# version1b.net
KiCad netlist of a schematic drawn in EAGLE
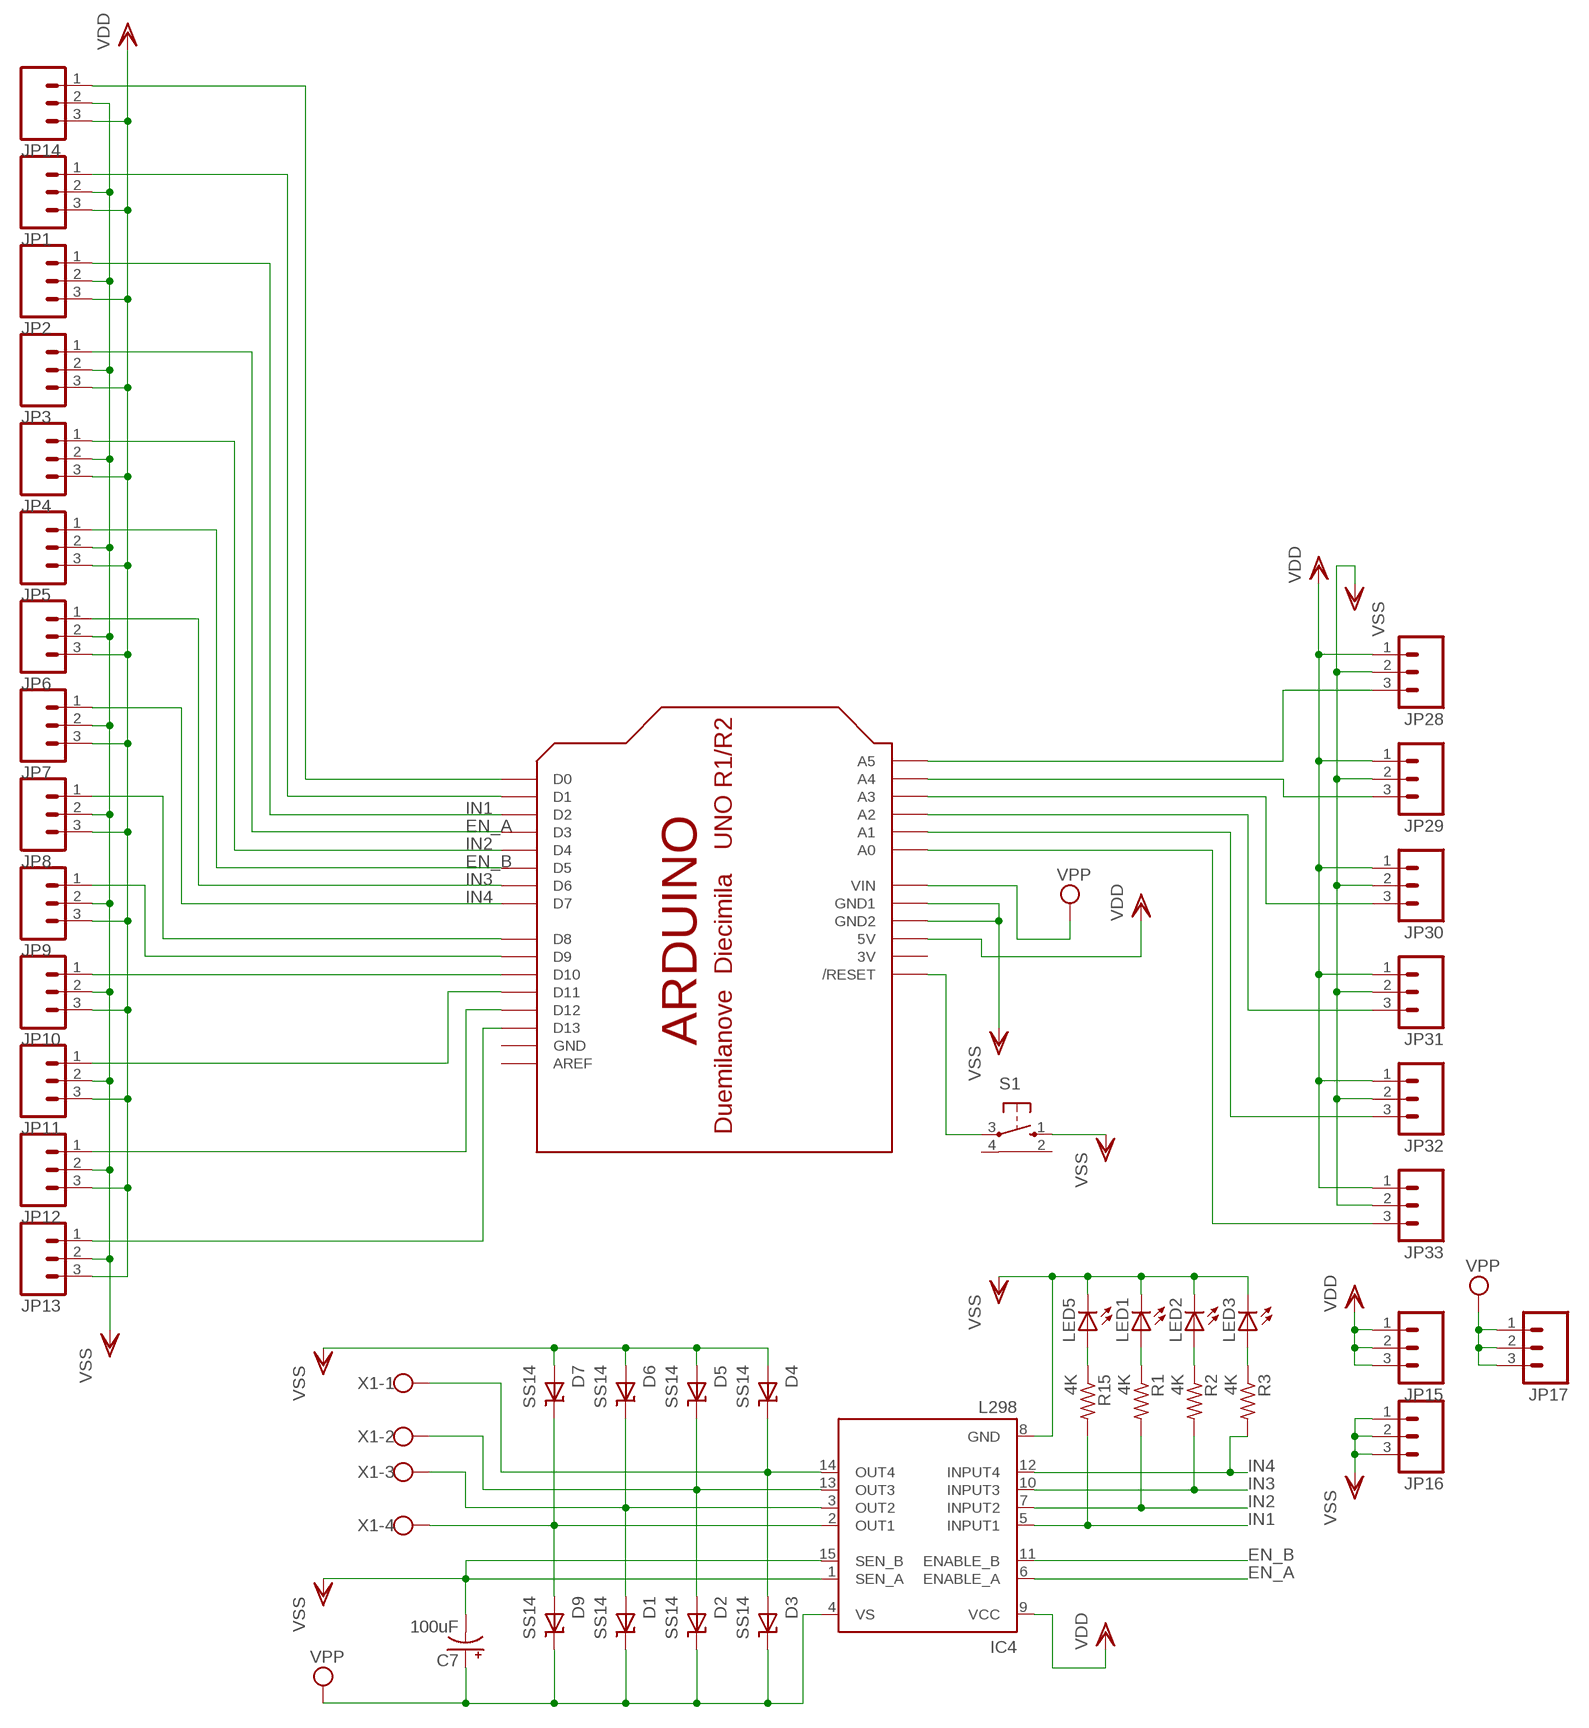
[diagram p0: schematic, sheet 1]

(export (version "E")
  (design (tool "Eeschema 10.0.6"))
  (components
    (comp (ref "C7")
      (value "100uF")
      (footprint "eagle-import:153CLV-0605")
      (libsource (lib "eagle-import") (part "CPOL-US153CLV-0605"))
    )
    (comp (ref "D1")
      (value "SS14")
      (footprint "eagle-import:SMA")
      (libsource (lib "eagle-import") (part "SS14"))
    )
    (comp (ref "D2")
      (value "SS14")
      (footprint "eagle-import:SMA")
      (libsource (lib "eagle-import") (part "SS14"))
    )
    (comp (ref "D3")
      (value "SS14")
      (footprint "eagle-import:SMA")
      (libsource (lib "eagle-import") (part "SS14"))
    )
    (comp (ref "D4")
      (value "SS14")
      (footprint "eagle-import:SMA")
      (libsource (lib "eagle-import") (part "SS14"))
    )
    (comp (ref "D5")
      (value "SS14")
      (footprint "eagle-import:SMA")
      (libsource (lib "eagle-import") (part "SS14"))
    )
    (comp (ref "D6")
      (value "SS14")
      (footprint "eagle-import:SMA")
      (libsource (lib "eagle-import") (part "SS14"))
    )
    (comp (ref "D7")
      (value "SS14")
      (footprint "eagle-import:SMA")
      (libsource (lib "eagle-import") (part "SS14"))
    )
    (comp (ref "D9")
      (value "SS14")
      (footprint "eagle-import:SMA")
      (libsource (lib "eagle-import") (part "SS14"))
    )
    (comp (ref "IC4")
      (value "L298")
      (footprint "eagle-import:MULTIWATT-15")
      (fields (field (name "MPN") "L298N"))
      (libsource (lib "eagle-import") (part "L298"))
    )
    (comp (ref "JP1")
      (value "M03PTH")
      (footprint "eagle-import:1X03")
      (libsource (lib "eagle-import") (part "M03PTH"))
    )
    (comp (ref "JP2")
      (value "M03PTH")
      (footprint "eagle-import:1X03")
      (libsource (lib "eagle-import") (part "M03PTH"))
    )
    (comp (ref "JP3")
      (value "M03PTH")
      (footprint "eagle-import:1X03")
      (libsource (lib "eagle-import") (part "M03PTH"))
    )
    (comp (ref "JP4")
      (value "M03PTH")
      (footprint "eagle-import:1X03")
      (libsource (lib "eagle-import") (part "M03PTH"))
    )
    (comp (ref "JP5")
      (value "M03PTH")
      (footprint "eagle-import:1X03")
      (libsource (lib "eagle-import") (part "M03PTH"))
    )
    (comp (ref "JP6")
      (value "M03PTH")
      (footprint "eagle-import:1X03")
      (libsource (lib "eagle-import") (part "M03PTH"))
    )
    (comp (ref "JP7")
      (value "M03PTH")
      (footprint "eagle-import:1X03")
      (libsource (lib "eagle-import") (part "M03PTH"))
    )
    (comp (ref "JP8")
      (value "M03PTH")
      (footprint "eagle-import:1X03")
      (libsource (lib "eagle-import") (part "M03PTH"))
    )
    (comp (ref "JP9")
      (value "M03PTH")
      (footprint "eagle-import:1X03")
      (libsource (lib "eagle-import") (part "M03PTH"))
    )
    (comp (ref "JP10")
      (value "M03PTH")
      (footprint "eagle-import:1X03")
      (libsource (lib "eagle-import") (part "M03PTH"))
    )
    (comp (ref "JP11")
      (value "M03PTH")
      (footprint "eagle-import:1X03")
      (libsource (lib "eagle-import") (part "M03PTH"))
    )
    (comp (ref "JP12")
      (value "M03PTH")
      (footprint "eagle-import:1X03")
      (libsource (lib "eagle-import") (part "M03PTH"))
    )
    (comp (ref "JP13")
      (value "M03PTH")
      (footprint "eagle-import:1X03")
      (libsource (lib "eagle-import") (part "M03PTH"))
    )
    (comp (ref "JP14")
      (value "M03PTH")
      (footprint "eagle-import:1X03")
      (libsource (lib "eagle-import") (part "M03PTH"))
    )
    (comp (ref "JP15")
      (value "M03PTH")
      (footprint "eagle-import:1X03")
      (libsource (lib "eagle-import") (part "M03PTH"))
    )
    (comp (ref "JP16")
      (value "M03PTH")
      (footprint "eagle-import:1X03")
      (libsource (lib "eagle-import") (part "M03PTH"))
    )
    (comp (ref "JP17")
      (value "M03PTH")
      (footprint "eagle-import:1X03")
      (libsource (lib "eagle-import") (part "M03PTH"))
    )
    (comp (ref "JP28")
      (value "M03PTH")
      (footprint "eagle-import:1X03")
      (libsource (lib "eagle-import") (part "M03PTH"))
    )
    (comp (ref "JP29")
      (value "M03PTH")
      (footprint "eagle-import:1X03")
      (libsource (lib "eagle-import") (part "M03PTH"))
    )
    (comp (ref "JP30")
      (value "M03PTH")
      (footprint "eagle-import:1X03")
      (libsource (lib "eagle-import") (part "M03PTH"))
    )
    (comp (ref "JP31")
      (value "M03PTH")
      (footprint "eagle-import:1X03")
      (libsource (lib "eagle-import") (part "M03PTH"))
    )
    (comp (ref "JP32")
      (value "M03PTH")
      (footprint "eagle-import:1X03")
      (libsource (lib "eagle-import") (part "M03PTH"))
    )
    (comp (ref "JP33")
      (value "M03PTH")
      (footprint "eagle-import:1X03")
      (libsource (lib "eagle-import") (part "M03PTH"))
    )
    (comp (ref "LED1")
      (value "LEDCHIP-LED0805")
      (footprint "eagle-import:CHIP-LED0805")
      (libsource (lib "eagle-import") (part "LEDCHIP-LED0805"))
    )
    (comp (ref "LED2")
      (value "LEDCHIP-LED0805")
      (footprint "eagle-import:CHIP-LED0805")
      (libsource (lib "eagle-import") (part "LEDCHIP-LED0805"))
    )
    (comp (ref "LED3")
      (value "LEDCHIP-LED0805")
      (footprint "eagle-import:CHIP-LED0805")
      (libsource (lib "eagle-import") (part "LEDCHIP-LED0805"))
    )
    (comp (ref "LED5")
      (value "LEDCHIP-LED0805")
      (footprint "eagle-import:CHIP-LED0805")
      (libsource (lib "eagle-import") (part "LEDCHIP-LED0805"))
    )
    (comp (ref "R1")
      (value "4K")
      (footprint "eagle-import:R0805")
      (libsource (lib "eagle-import") (part "R-US_R0805"))
    )
    (comp (ref "R2")
      (value "4K")
      (footprint "eagle-import:R0805")
      (libsource (lib "eagle-import") (part "R-US_R0805"))
    )
    (comp (ref "R3")
      (value "4K")
      (footprint "eagle-import:R0805")
      (libsource (lib "eagle-import") (part "R-US_R0805"))
    )
    (comp (ref "R15")
      (value "4K")
      (footprint "eagle-import:R0805")
      (libsource (lib "eagle-import") (part "R-US_R0805"))
    )
    (comp (ref "S1")
      (value "10-XX-RPAD")
      (footprint "eagle-import:B3F-10XX-RPAD")
      (libsource (lib "eagle-import") (part "10-XX-RPAD"))
    )
    (comp (ref "U$1")
      (value "ARDUINO-NOHOLE")
      (footprint "eagle-import:ARDUINO-NOHOLE")
      (libsource (lib "eagle-import") (part "ARDUINO-NOHOLE"))
    )
    (comp (ref "X1")
      (value "W237-4")
      (footprint "eagle-import:W237-4")
      (libsource (lib "eagle-import") (part "W237-4"))
    )
  )
  (nets
    (net (code "1") (name "/3V") (class "Default")
      (node (ref "U$1") (pin "3V") (pinfunction "3V_3V") (pintype "power_in"))
    )
    (net (code "2") (name "/EN_A") (class "Default")
      (node (ref "IC4") (pin "6") (pinfunction "ENABLE_A_6") (pintype "input"))
      (node (ref "JP3") (pin "1") (pinfunction "1_1") (pintype "passive"))
      (node (ref "U$1") (pin "D3") (pinfunction "D3_D3") (pintype "bidirectional"))
    )
    (net (code "3") (name "/EN_B") (class "Default")
      (node (ref "IC4") (pin "11") (pinfunction "ENABLE_B_11") (pintype "input"))
      (node (ref "JP5") (pin "1") (pinfunction "1_1") (pintype "passive"))
      (node (ref "U$1") (pin "D5") (pinfunction "D5_D5") (pintype "bidirectional"))
    )
    (net (code "4") (name "/GND") (class "Default")
      (node (ref "U$1") (pin "GND") (pinfunction "GND_GND") (pintype "power_in"))
    )
    (net (code "5") (name "/IN1") (class "Default")
      (node (ref "IC4") (pin "5") (pinfunction "INPUT1_5") (pintype "input"))
      (node (ref "JP2") (pin "1") (pinfunction "1_1") (pintype "passive"))
      (node (ref "R15") (pin "2") (pinfunction "2_2") (pintype "passive"))
      (node (ref "U$1") (pin "D2") (pinfunction "D2_D2") (pintype "bidirectional"))
    )
    (net (code "6") (name "/IN2") (class "Default")
      (node (ref "IC4") (pin "7") (pinfunction "INPUT2_7") (pintype "input"))
      (node (ref "JP4") (pin "1") (pinfunction "1_1") (pintype "passive"))
      (node (ref "R1") (pin "2") (pinfunction "2_2") (pintype "passive"))
      (node (ref "U$1") (pin "D4") (pinfunction "D4_D4") (pintype "bidirectional"))
    )
    (net (code "7") (name "/IN3") (class "Default")
      (node (ref "IC4") (pin "10") (pinfunction "INPUT3_10") (pintype "input"))
      (node (ref "JP6") (pin "1") (pinfunction "1_1") (pintype "passive"))
      (node (ref "R2") (pin "2") (pinfunction "2_2") (pintype "passive"))
      (node (ref "U$1") (pin "D6") (pinfunction "D6_D6") (pintype "bidirectional"))
    )
    (net (code "8") (name "/IN4") (class "Default")
      (node (ref "IC4") (pin "12") (pinfunction "INPUT4_12") (pintype "input"))
      (node (ref "JP7") (pin "1") (pinfunction "1_1") (pintype "passive"))
      (node (ref "R3") (pin "2") (pinfunction "2_2") (pintype "passive"))
      (node (ref "U$1") (pin "D7") (pinfunction "D7_D7") (pintype "bidirectional"))
    )
    (net (code "9") (name "Net-(D1-A)") (class "Default")
      (node (ref "D1") (pin "P$2") (pinfunction "A_P$2") (pintype "bidirectional"))
      (node (ref "D6") (pin "P$1") (pinfunction "K_P$1") (pintype "bidirectional"))
      (node (ref "IC4") (pin "3") (pinfunction "OUT2_3") (pintype "output"))
      (node (ref "X1") (pin "3") (pinfunction "KL_3") (pintype "passive"))
    )
    (net (code "10") (name "Net-(D2-A)") (class "Default")
      (node (ref "D2") (pin "P$2") (pinfunction "A_P$2") (pintype "bidirectional"))
      (node (ref "D5") (pin "P$1") (pinfunction "K_P$1") (pintype "bidirectional"))
      (node (ref "IC4") (pin "13") (pinfunction "OUT3_13") (pintype "output"))
      (node (ref "X1") (pin "2") (pinfunction "KL_2") (pintype "passive"))
    )
    (net (code "11") (name "Net-(D3-A)") (class "Default")
      (node (ref "D3") (pin "P$2") (pinfunction "A_P$2") (pintype "bidirectional"))
      (node (ref "D4") (pin "P$1") (pinfunction "K_P$1") (pintype "bidirectional"))
      (node (ref "IC4") (pin "14") (pinfunction "OUT4_14") (pintype "output"))
      (node (ref "X1") (pin "1") (pinfunction "KL_1") (pintype "passive"))
    )
    (net (code "12") (name "Net-(D7-K)") (class "Default")
      (node (ref "D7") (pin "P$1") (pinfunction "K_P$1") (pintype "bidirectional"))
      (node (ref "D9") (pin "P$2") (pinfunction "A_P$2") (pintype "bidirectional"))
      (node (ref "IC4") (pin "2") (pinfunction "OUT1_2") (pintype "output"))
      (node (ref "X1") (pin "4") (pinfunction "KL_4") (pintype "passive"))
    )
    (net (code "13") (name "Net-(JP1-Pad1)") (class "Default")
      (node (ref "JP1") (pin "1") (pinfunction "1_1") (pintype "passive"))
      (node (ref "U$1") (pin "D1") (pinfunction "D1_D1") (pintype "bidirectional"))
    )
    (net (code "14") (name "Net-(JP8-Pad1)") (class "Default")
      (node (ref "JP8") (pin "1") (pinfunction "1_1") (pintype "passive"))
      (node (ref "U$1") (pin "D8") (pinfunction "D8_D8") (pintype "bidirectional"))
    )
    (net (code "15") (name "Net-(JP9-Pad1)") (class "Default")
      (node (ref "JP9") (pin "1") (pinfunction "1_1") (pintype "passive"))
      (node (ref "U$1") (pin "D9") (pinfunction "D9_D9") (pintype "bidirectional"))
    )
    (net (code "16") (name "Net-(JP10-Pad1)") (class "Default")
      (node (ref "JP10") (pin "1") (pinfunction "1_1") (pintype "passive"))
      (node (ref "U$1") (pin "D10") (pinfunction "D10_D10") (pintype "bidirectional"))
    )
    (net (code "17") (name "Net-(JP11-Pad1)") (class "Default")
      (node (ref "JP11") (pin "1") (pinfunction "1_1") (pintype "passive"))
      (node (ref "U$1") (pin "D11") (pinfunction "D11_D11") (pintype "bidirectional"))
    )
    (net (code "18") (name "Net-(JP12-Pad1)") (class "Default")
      (node (ref "JP12") (pin "1") (pinfunction "1_1") (pintype "passive"))
      (node (ref "U$1") (pin "D12") (pinfunction "D12_D12") (pintype "bidirectional"))
    )
    (net (code "19") (name "Net-(JP13-Pad1)") (class "Default")
      (node (ref "JP13") (pin "1") (pinfunction "1_1") (pintype "passive"))
      (node (ref "U$1") (pin "D13") (pinfunction "D13_D13") (pintype "bidirectional"))
    )
    (net (code "20") (name "Net-(JP14-Pad1)") (class "Default")
      (node (ref "JP14") (pin "1") (pinfunction "1_1") (pintype "passive"))
      (node (ref "U$1") (pin "D0") (pinfunction "D0_D0") (pintype "bidirectional"))
    )
    (net (code "21") (name "Net-(JP28-Pad3)") (class "Default")
      (node (ref "JP28") (pin "3") (pinfunction "3_3") (pintype "passive"))
      (node (ref "U$1") (pin "A5") (pinfunction "A5_A5") (pintype "bidirectional"))
    )
    (net (code "22") (name "Net-(JP29-Pad3)") (class "Default")
      (node (ref "JP29") (pin "3") (pinfunction "3_3") (pintype "passive"))
      (node (ref "U$1") (pin "A4") (pinfunction "A4_A4") (pintype "bidirectional"))
    )
    (net (code "23") (name "Net-(JP30-Pad3)") (class "Default")
      (node (ref "JP30") (pin "3") (pinfunction "3_3") (pintype "passive"))
      (node (ref "U$1") (pin "A3") (pinfunction "A3_A3") (pintype "bidirectional"))
    )
    (net (code "24") (name "Net-(JP31-Pad3)") (class "Default")
      (node (ref "JP31") (pin "3") (pinfunction "3_3") (pintype "passive"))
      (node (ref "U$1") (pin "A2") (pinfunction "A2_A2") (pintype "bidirectional"))
    )
    (net (code "25") (name "Net-(JP32-Pad3)") (class "Default")
      (node (ref "JP32") (pin "3") (pinfunction "3_3") (pintype "passive"))
      (node (ref "U$1") (pin "A1") (pinfunction "A1_A1") (pintype "bidirectional"))
    )
    (net (code "26") (name "Net-(JP33-Pad3)") (class "Default")
      (node (ref "JP33") (pin "3") (pinfunction "3_3") (pintype "passive"))
      (node (ref "U$1") (pin "A0") (pinfunction "A0_A0") (pintype "bidirectional"))
    )
    (net (code "27") (name "Net-(LED1-PadA)") (class "Default")
      (node (ref "LED1") (pin "A") (pinfunction "A_A") (pintype "passive"))
      (node (ref "R1") (pin "1") (pinfunction "1_1") (pintype "passive"))
    )
    (net (code "28") (name "Net-(LED2-PadA)") (class "Default")
      (node (ref "LED2") (pin "A") (pinfunction "A_A") (pintype "passive"))
      (node (ref "R2") (pin "1") (pinfunction "1_1") (pintype "passive"))
    )
    (net (code "29") (name "Net-(LED3-PadA)") (class "Default")
      (node (ref "LED3") (pin "A") (pinfunction "A_A") (pintype "passive"))
      (node (ref "R3") (pin "1") (pinfunction "1_1") (pintype "passive"))
    )
    (net (code "30") (name "Net-(LED5-PadA)") (class "Default")
      (node (ref "LED5") (pin "A") (pinfunction "A_A") (pintype "passive"))
      (node (ref "R15") (pin "1") (pinfunction "1_1") (pintype "passive"))
    )
    (net (code "31") (name "Net-(S1-P)") (class "Default")
      (node (ref "S1") (pin "3") (pinfunction "P_3") (pintype "passive"))
      (node (ref "U$1") (pin "RESET") (pinfunction "/RESET_RESET") (pintype "bidirectional"))
    )
    (net (code "32") (name "VDD") (class "Default")
      (node (ref "IC4") (pin "9") (pinfunction "VCC_9") (pintype "power_in"))
      (node (ref "JP1") (pin "3") (pinfunction "3_3") (pintype "passive"))
      (node (ref "JP10") (pin "3") (pinfunction "3_3") (pintype "passive"))
      (node (ref "JP11") (pin "3") (pinfunction "3_3") (pintype "passive"))
      (node (ref "JP12") (pin "3") (pinfunction "3_3") (pintype "passive"))
      (node (ref "JP13") (pin "3") (pinfunction "3_3") (pintype "passive"))
      (node (ref "JP14") (pin "3") (pinfunction "3_3") (pintype "passive"))
      (node (ref "JP15") (pin "1") (pinfunction "1_1") (pintype "passive"))
      (node (ref "JP15") (pin "2") (pinfunction "2_2") (pintype "passive"))
      (node (ref "JP15") (pin "3") (pinfunction "3_3") (pintype "passive"))
      (node (ref "JP2") (pin "3") (pinfunction "3_3") (pintype "passive"))
      (node (ref "JP28") (pin "1") (pinfunction "1_1") (pintype "passive"))
      (node (ref "JP29") (pin "1") (pinfunction "1_1") (pintype "passive"))
      (node (ref "JP3") (pin "3") (pinfunction "3_3") (pintype "passive"))
      (node (ref "JP30") (pin "1") (pinfunction "1_1") (pintype "passive"))
      (node (ref "JP31") (pin "1") (pinfunction "1_1") (pintype "passive"))
      (node (ref "JP32") (pin "1") (pinfunction "1_1") (pintype "passive"))
      (node (ref "JP33") (pin "1") (pinfunction "1_1") (pintype "passive"))
      (node (ref "JP4") (pin "3") (pinfunction "3_3") (pintype "passive"))
      (node (ref "JP5") (pin "3") (pinfunction "3_3") (pintype "passive"))
      (node (ref "JP6") (pin "3") (pinfunction "3_3") (pintype "passive"))
      (node (ref "JP7") (pin "3") (pinfunction "3_3") (pintype "passive"))
      (node (ref "JP8") (pin "3") (pinfunction "3_3") (pintype "passive"))
      (node (ref "JP9") (pin "3") (pinfunction "3_3") (pintype "passive"))
      (node (ref "U$1") (pin "5V") (pinfunction "5V_5V") (pintype "power_in"))
    )
    (net (code "33") (name "VPP") (class "Default")
      (node (ref "C7") (pin "+") (pinfunction "+_+") (pintype "passive"))
      (node (ref "D1") (pin "P$1") (pinfunction "K_P$1") (pintype "bidirectional"))
      (node (ref "D2") (pin "P$1") (pinfunction "K_P$1") (pintype "bidirectional"))
      (node (ref "D3") (pin "P$1") (pinfunction "K_P$1") (pintype "bidirectional"))
      (node (ref "D9") (pin "P$1") (pinfunction "K_P$1") (pintype "bidirectional"))
      (node (ref "IC4") (pin "4") (pinfunction "VS_4") (pintype "power_in"))
      (node (ref "JP17") (pin "1") (pinfunction "1_1") (pintype "passive"))
      (node (ref "JP17") (pin "2") (pinfunction "2_2") (pintype "passive"))
      (node (ref "JP17") (pin "3") (pinfunction "3_3") (pintype "passive"))
      (node (ref "U$1") (pin "VIN") (pinfunction "VIN_VIN") (pintype "power_in"))
    )
    (net (code "34") (name "VSS") (class "Default")
      (node (ref "C7") (pin "-") (pinfunction "-_-") (pintype "passive"))
      (node (ref "D4") (pin "P$2") (pinfunction "A_P$2") (pintype "bidirectional"))
      (node (ref "D5") (pin "P$2") (pinfunction "A_P$2") (pintype "bidirectional"))
      (node (ref "D6") (pin "P$2") (pinfunction "A_P$2") (pintype "bidirectional"))
      (node (ref "D7") (pin "P$2") (pinfunction "A_P$2") (pintype "bidirectional"))
      (node (ref "IC4") (pin "1") (pinfunction "SEN_A_1") (pintype "input"))
      (node (ref "IC4") (pin "15") (pinfunction "SEN_B_15") (pintype "input"))
      (node (ref "IC4") (pin "8") (pinfunction "GND_8") (pintype "power_in"))
      (node (ref "JP1") (pin "2") (pinfunction "2_2") (pintype "passive"))
      (node (ref "JP10") (pin "2") (pinfunction "2_2") (pintype "passive"))
      (node (ref "JP11") (pin "2") (pinfunction "2_2") (pintype "passive"))
      (node (ref "JP12") (pin "2") (pinfunction "2_2") (pintype "passive"))
      (node (ref "JP13") (pin "2") (pinfunction "2_2") (pintype "passive"))
      (node (ref "JP14") (pin "2") (pinfunction "2_2") (pintype "passive"))
      (node (ref "JP16") (pin "1") (pinfunction "1_1") (pintype "passive"))
      (node (ref "JP16") (pin "2") (pinfunction "2_2") (pintype "passive"))
      (node (ref "JP16") (pin "3") (pinfunction "3_3") (pintype "passive"))
      (node (ref "JP2") (pin "2") (pinfunction "2_2") (pintype "passive"))
      (node (ref "JP28") (pin "2") (pinfunction "2_2") (pintype "passive"))
      (node (ref "JP29") (pin "2") (pinfunction "2_2") (pintype "passive"))
      (node (ref "JP3") (pin "2") (pinfunction "2_2") (pintype "passive"))
      (node (ref "JP30") (pin "2") (pinfunction "2_2") (pintype "passive"))
      (node (ref "JP31") (pin "2") (pinfunction "2_2") (pintype "passive"))
      (node (ref "JP32") (pin "2") (pinfunction "2_2") (pintype "passive"))
      (node (ref "JP33") (pin "2") (pinfunction "2_2") (pintype "passive"))
      (node (ref "JP4") (pin "2") (pinfunction "2_2") (pintype "passive"))
      (node (ref "JP5") (pin "2") (pinfunction "2_2") (pintype "passive"))
      (node (ref "JP6") (pin "2") (pinfunction "2_2") (pintype "passive"))
      (node (ref "JP7") (pin "2") (pinfunction "2_2") (pintype "passive"))
      (node (ref "JP8") (pin "2") (pinfunction "2_2") (pintype "passive"))
      (node (ref "JP9") (pin "2") (pinfunction "2_2") (pintype "passive"))
      (node (ref "LED1") (pin "C") (pinfunction "C_C") (pintype "passive"))
      (node (ref "LED2") (pin "C") (pinfunction "C_C") (pintype "passive"))
      (node (ref "LED3") (pin "C") (pinfunction "C_C") (pintype "passive"))
      (node (ref "LED5") (pin "C") (pinfunction "C_C") (pintype "passive"))
      (node (ref "S1") (pin "1") (pinfunction "S_1") (pintype "passive"))
      (node (ref "U$1") (pin "GND1") (pinfunction "GND1_GND1") (pintype "power_in"))
      (node (ref "U$1") (pin "GND2") (pinfunction "GND2_GND2") (pintype "power_in"))
    )
    (net (code "35") (name "unconnected-(S1-GND1-Pad2)") (class "Default")
      (node (ref "S1") (pin "2") (pinfunction "GND1_2") (pintype "passive"))
    )
    (net (code "36") (name "unconnected-(S1-GND2-Pad4)") (class "Default")
      (node (ref "S1") (pin "4") (pinfunction "GND2_4") (pintype "passive"))
    )
    (net (code "37") (name "unconnected-(U$1-PadAREF)") (class "Default")
      (node (ref "U$1") (pin "AREF") (pinfunction "AREF_AREF") (pintype "bidirectional"))
    )
  )
)
